# SHDN-BSPD-S09-V00-ShutdownRelay.net
KiCad netlist of a schematic drawn in Altium Designer
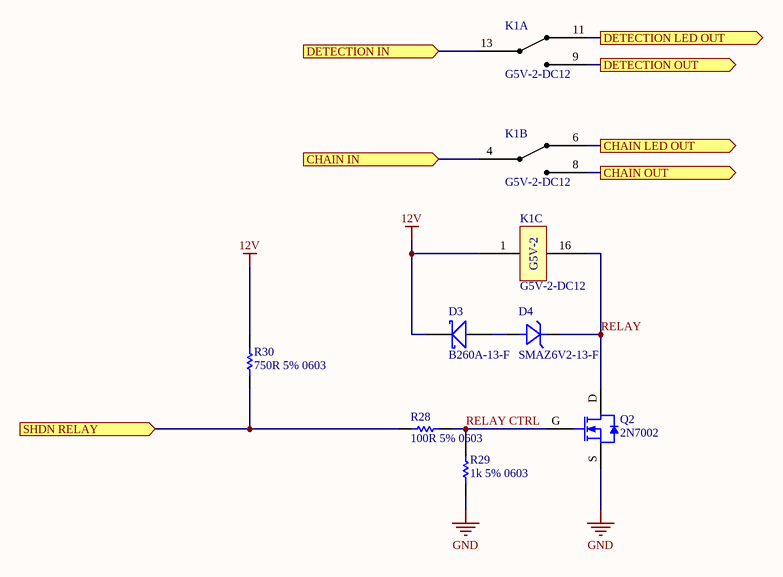
[diagram p0: SHDN-BSPD-S09-V00-ShutdownRelay.SchDoc]

(export (version "E")
  (design (tool "Eeschema 10.0.6"))
  (components
    (comp (ref "D3")
      (value "B260A-13-F")
      (footprint "SMA")
      (description "Diode, Schottky Barrier Rectifier, 60 V, 2 A, B260A-13-F")
      (libsource (lib "QUTMS_DiodeLibrary") (part "B260A-13-F"))
    )
    (comp (ref "D4")
      (value "SMAZ6V2-13-F")
      (footprint "SMA")
      (description "Zener Diode 6.2V 1W ±5% Surface Mount SMA")
      (fields (field (name "MANUFACTURER") "Generic") (field (name "MPN") "5V6 500mW SMA"))
      (libsource (lib "QUTMS_DiodeLibrary") (part "SMAZ6V2-13-F"))
    )
    (comp (ref "K1")
      (value "G5V-2-DC12")
      (footprint "G5V-2")
      (description "General Purpose Relay DPDT (2 Form C) Through Hole, 12V, 2A")
      (libsource (lib "QUTMS_RelayLibrary") (part "G5V-2-DC12"))
    )
    (comp (ref "Q2")
      (value "2N7002")
      (footprint "SOT23-3")
      (libsource (lib "QUTMS_MOSFETLibrary") (part "2N7002"))
    )
    (comp (ref "R28")
      (value "100R 5% 0603")
      (footprint "Res_ThinFilm_0603")
      (description "Resistor, SMD, 100R, 0.1W, 5%, 0603")
      (libsource (lib "StandardResistors") (part "100R 5%, 0603"))
    )
    (comp (ref "R29")
      (value "1k 5% 0603")
      (footprint "Res_ThinFilm_0603")
      (description "Resistor, SMD, 1k, 0.1W, 5%, 0603")
      (libsource (lib "StandardResistors") (part "1k 5% 0603"))
    )
    (comp (ref "R30")
      (value "750R 5% 0603")
      (footprint "Res_ThinFilm_0603")
      (description "Resistor, SMD, 750R, 0.1W, 5%, 0603")
      (libsource (lib "StandardResistors") (part "820R 5% 0603"))
    )
  )
  (nets
    (net (code "1") (name "/CHAIN IN") (class "Default")
      (node (ref "K1") (pin "4") (pinfunction "4_4") (pintype "passive"))
    )
    (net (code "2") (name "/CHAIN LED OUT") (class "Default")
      (node (ref "K1") (pin "6") (pinfunction "6_6") (pintype "passive"))
    )
    (net (code "3") (name "/CHAIN OUT") (class "Default")
      (node (ref "K1") (pin "8") (pinfunction "8_8") (pintype "passive"))
    )
    (net (code "4") (name "/DETECTION IN") (class "Default")
      (node (ref "K1") (pin "13") (pinfunction "13_13") (pintype "passive"))
    )
    (net (code "5") (name "/DETECTION LED OUT") (class "Default")
      (node (ref "K1") (pin "11") (pinfunction "11_11") (pintype "passive"))
    )
    (net (code "6") (name "/DETECTION OUT") (class "Default")
      (node (ref "K1") (pin "9") (pinfunction "9_9") (pintype "passive"))
    )
    (net (code "7") (name "/RELAY") (class "Default")
      (node (ref "D4") (pin "K") (pinfunction "Cathode_K") (pintype "passive"))
      (node (ref "K1") (pin "16") (pinfunction "16_16") (pintype "passive"))
      (node (ref "Q2") (pin "D") (pinfunction "D_D") (pintype "passive"))
    )
    (net (code "8") (name "/RELAY CTRL") (class "Default")
      (node (ref "Q2") (pin "G") (pinfunction "G_G") (pintype "passive"))
      (node (ref "R28") (pin "2") (pinfunction "2_2") (pintype "passive"))
      (node (ref "R29") (pin "2") (pinfunction "2_2") (pintype "passive"))
    )
    (net (code "9") (name "/SHDN RELAY") (class "Default")
      (node (ref "R28") (pin "1") (pinfunction "1_1") (pintype "passive"))
      (node (ref "R30") (pin "1") (pinfunction "1_1") (pintype "passive"))
    )
    (net (code "10") (name "12V") (class "Default")
      (node (ref "D3") (pin "K") (pinfunction "K_K") (pintype "passive"))
      (node (ref "K1") (pin "1") (pinfunction "1_1") (pintype "passive"))
      (node (ref "R30") (pin "2") (pinfunction "2_2") (pintype "passive"))
    )
    (net (code "11") (name "GND") (class "Default")
      (node (ref "Q2") (pin "S") (pinfunction "S_S") (pintype "passive"))
      (node (ref "R29") (pin "1") (pinfunction "1_1") (pintype "passive"))
    )
    (net (code "12") (name "Net-(D4-Anode)") (class "Default")
      (node (ref "D3") (pin "A") (pinfunction "A_A") (pintype "passive"))
      (node (ref "D4") (pin "A") (pinfunction "Anode_A") (pintype "passive"))
    )
  )
)
